# CAN_Transceiver_3V3.net
KiCad netlist of a schematic drawn in Altium Designer
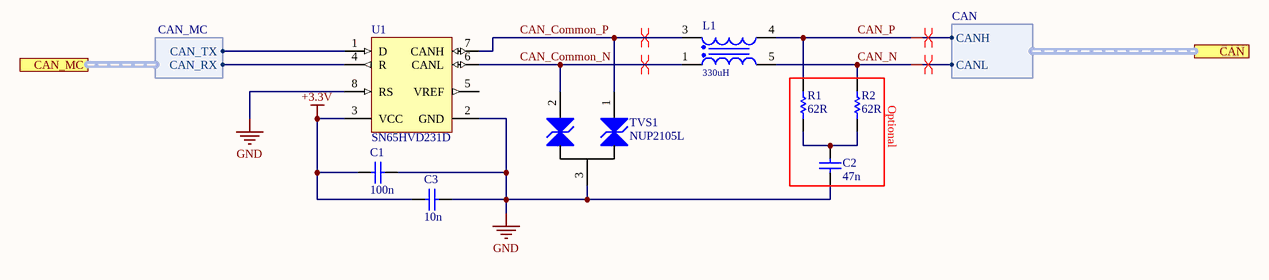
[diagram p0: CAN_Transceiver_3V3.SchDoc]

(export (version "E")
  (design (tool "Eeschema 10.0.6"))
  (components
    (comp (ref "C1")
      (value "100n")
      (footprint "CAPC0603(1608)55_N")
      (description "Keramikvielschichtkondensator, SMD, Baureihe MC, ± 10%")
      (fields (field (name "MANUFACTURER") "TDK") (field (name "TOLERANCE") "± 10%"))
      (libsource (lib "Res&Caps") (part "Cap 100n"))
    )
    (comp (ref "C2")
      (value "47n")
      (footprint "CAPC0603(1608)55_N")
      (description "Keramikvielschichtkondensator, SMD, Baureihe MC, ± 10%")
      (fields (field (name "MANUFACTURER") "TDK") (field (name "TOLERANCE") "± 10%"))
      (libsource (lib "Res&Caps") (part "Cap 47n"))
    )
    (comp (ref "C3")
      (value "10n")
      (footprint "CAPC0603(1608)55_N")
      (description "Keramikvielschichtkondensator, SMD, Baureihe MC, ± 10%")
      (fields (field (name "MANUFACTURER") "TDK") (field (name "TOLERANCE") "± 10%"))
      (libsource (lib "Res&Caps") (part "Cap 10n"))
    )
    (comp (ref "L1")
      (value "330uH")
      (footprint "WE-SL1")
      (description "WE-SL1 SMT Common Mode Line Filter, 330uH, 300mA, 80V")
      (fields
        (field (name "MANUFACTURER") "Wurth Elektronik")
        (field (name "MANUFACTURER PART NUMBER") "744212331")
      )
      (libsource (lib "LV-BMS") (part "744212331"))
    )
    (comp (ref "R1")
      (value "62R")
      (footprint "RESC0603(1608)_N")
      (description "Chipwiderstand, SMD, Baureihe MC, 1%")
      (fields (field (name "MANUFACTURER") "Multicomp") (field (name "POWER") "100mW"))
      (libsource (lib "Res&Caps") (part "Res 62R"))
    )
    (comp (ref "R2")
      (value "62R")
      (footprint "RESC0603(1608)_N")
      (description "Chipwiderstand, SMD, Baureihe MC, 1%")
      (fields (field (name "MANUFACTURER") "Multicomp") (field (name "POWER") "100mW"))
      (libsource (lib "Res&Caps") (part "Res 62R"))
    )
    (comp (ref "TVS1")
      (value "NUP2105L")
      (footprint "_SOT23-3N")
      (description "Dual Bidirectional Voltage Suppressor 350W Peak")
      (libsource (lib "LV-BMS") (part "NUP2105L"))
    )
    (comp (ref "U1")
      (value "SN65HVD231D")
      (footprint "D0008A_L")
      (fields (field (name "MANUFACTURER") "Texas Instruments"))
      (libsource (lib "Altium Content Vault") (part "TI-SN65HVD231-SOIC_D-8"))
    )
  )
  (nets
    (net (code "3") (name "+3.3V") (class "Default")
      (node (ref "C1") (pin "1") (pinfunction "1_1") (pintype "passive"))
      (node (ref "C3") (pin "1") (pinfunction "1_1") (pintype "passive"))
      (node (ref "U1") (pin "3") (pinfunction "VCC_3") (pintype "power_in"))
    )
    (net (code "4") (name "/CAN_Common_N") (class "Default")
      (node (ref "L1") (pin "1") (pinfunction "1_1") (pintype "passive"))
      (node (ref "TVS1") (pin "2") (pinfunction "A2_2") (pintype "passive"))
      (node (ref "U1") (pin "6") (pinfunction "CANL_6") (pintype "bidirectional"))
    )
    (net (code "5") (name "/CAN_Common_P") (class "Default")
      (node (ref "L1") (pin "3") (pinfunction "3_3") (pintype "passive"))
      (node (ref "TVS1") (pin "1") (pinfunction "A1_1") (pintype "passive"))
      (node (ref "U1") (pin "7") (pinfunction "CANH_7") (pintype "bidirectional"))
    )
    (net (code "6") (name "/CAN_N") (class "Default")
      (node (ref "L1") (pin "5") (pinfunction "5_5") (pintype "passive"))
      (node (ref "R2") (pin "2") (pinfunction "2_2") (pintype "passive"))
    )
    (net (code "7") (name "/CAN_P") (class "Default")
      (node (ref "L1") (pin "4") (pinfunction "4_4") (pintype "passive"))
      (node (ref "R1") (pin "2") (pinfunction "2_2") (pintype "passive"))
    )
    (net (code "8") (name "/CAN_RX") (class "Default")
      (node (ref "U1") (pin "4") (pinfunction "R_4") (pintype "output"))
    )
    (net (code "9") (name "/CAN_TX") (class "Default")
      (node (ref "U1") (pin "1") (pinfunction "D_1") (pintype "input"))
    )
    (net (code "12") (name "GND") (class "Default")
      (node (ref "C1") (pin "2") (pinfunction "2_2") (pintype "passive"))
      (node (ref "C2") (pin "1") (pinfunction "1_1") (pintype "passive"))
      (node (ref "C3") (pin "2") (pinfunction "2_2") (pintype "passive"))
      (node (ref "TVS1") (pin "3") (pinfunction "A3_3") (pintype "passive"))
      (node (ref "U1") (pin "2") (pinfunction "GND_2") (pintype "power_in"))
      (node (ref "U1") (pin "8") (pinfunction "RS_8") (pintype "input"))
    )
    (net (code "13") (name "Net-(C2-Pad2)") (class "Default")
      (node (ref "C2") (pin "2") (pinfunction "2_2") (pintype "passive"))
      (node (ref "R1") (pin "1") (pinfunction "1_1") (pintype "passive"))
      (node (ref "R2") (pin "1") (pinfunction "1_1") (pintype "passive"))
    )
    (net (code "14") (name "unconnected-(U1-VREF-Pad5)") (class "Default")
      (node (ref "U1") (pin "5") (pinfunction "VREF_5") (pintype "output"))
    )
  )
)
